# Sheet1.net
KiCad netlist of a schematic drawn in Altium Designer
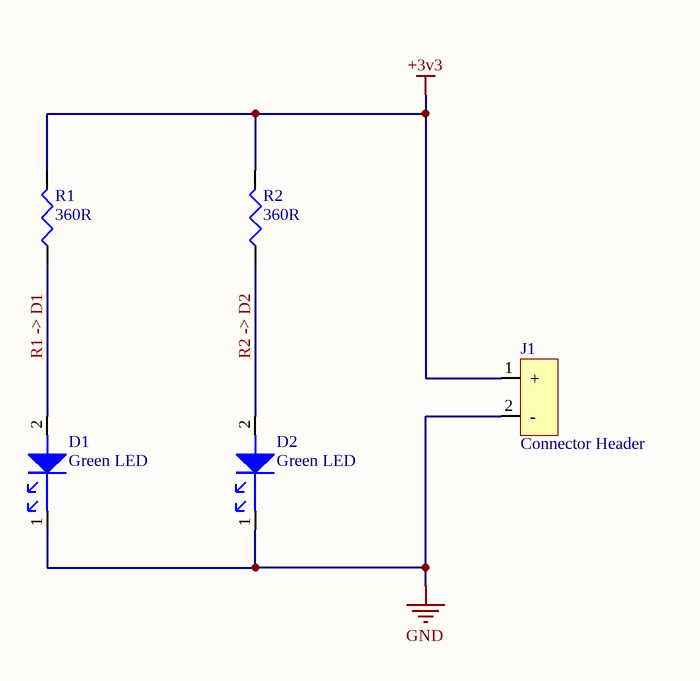
[diagram p0: Sheet1.SchDoc]

(export (version "E")
  (design (tool "Eeschema 10.0.6"))
  (components
    (comp (ref "D1")
      (value "Green LED")
      (footprint "Led_0603")
      (description "Green 572nm LED Indication - Discrete 2V 0603 (1608 Metric)")
      (fields (field (name "MANUFACTURER") "VCC") (field (name "MANUFACTURER PART NUMBER") "LSM0603453V"))
      (libsource (lib "Schlib1") (part "Diode LED"))
    )
    (comp (ref "D2")
      (value "Green LED")
      (footprint "Led_0603")
      (description "Green 572nm LED Indication - Discrete 2V 0603 (1608 Metric)")
      (fields (field (name "MANUFACTURER") "VCC") (field (name "MANUFACTURER PART NUMBER") "LSM0603453V"))
      (libsource (lib "Schlib1") (part "Diode LED"))
    )
    (comp (ref "J1")
      (value "Connector Header")
      (footprint "Header_1x2")
      (description "KK 254 Wire-to-Board Header, Vertical, with Friction Lock, 2 Circuits, Tin (Sn) Plating")
      (fields (field (name "MANUFACTURER") "Molex") (field (name "MANUFACTURER PART NUMBER") "22-27-2021"))
      (libsource (lib "Schlib1") (part "Connector Header"))
    )
    (comp (ref "R1")
      (value "360R")
      (footprint "R0805")
      (fields
        (field (name "MANUFACTURER") "Yageo Group")
        (field (name "MANUFACTURER PART NUMBER") "AC0805FR-07360RL")
        (field (name "TOLERANCE") "1%")
      )
      (libsource (lib "Schlib1") (part "Resistor"))
    )
    (comp (ref "R2")
      (value "360R")
      (footprint "R0805")
      (fields
        (field (name "MANUFACTURER") "Yageo Group")
        (field (name "MANUFACTURER PART NUMBER") "AC0805FR-07360RL")
        (field (name "TOLERANCE") "1%")
      )
      (libsource (lib "Schlib1") (part "Resistor"))
    )
  )
  (nets
    (net (code "1") (name "+3v3") (class "Default")
      (node (ref "J1") (pin "1") (pinfunction "+_1") (pintype "passive"))
      (node (ref "R1") (pin "2") (pinfunction "2_2") (pintype "passive"))
      (node (ref "R2") (pin "2") (pinfunction "2_2") (pintype "passive"))
    )
    (net (code "2") (name "/R1 -> D1") (class "Default")
      (node (ref "D1") (pin "2") (pinfunction "3_2") (pintype "passive"))
      (node (ref "R1") (pin "1") (pinfunction "1_1") (pintype "passive"))
    )
    (net (code "3") (name "/R2 -> D2") (class "Default")
      (node (ref "D2") (pin "2") (pinfunction "3_2") (pintype "passive"))
      (node (ref "R2") (pin "1") (pinfunction "1_1") (pintype "passive"))
    )
    (net (code "4") (name "GND") (class "Default")
      (node (ref "D1") (pin "1") (pinfunction "1_1") (pintype "passive"))
      (node (ref "D2") (pin "1") (pinfunction "1_1") (pintype "passive"))
      (node (ref "J1") (pin "2") (pinfunction "-_2") (pintype "passive"))
    )
  )
)
